# SynthV1.net
KiCad netlist of a schematic drawn in EAGLE
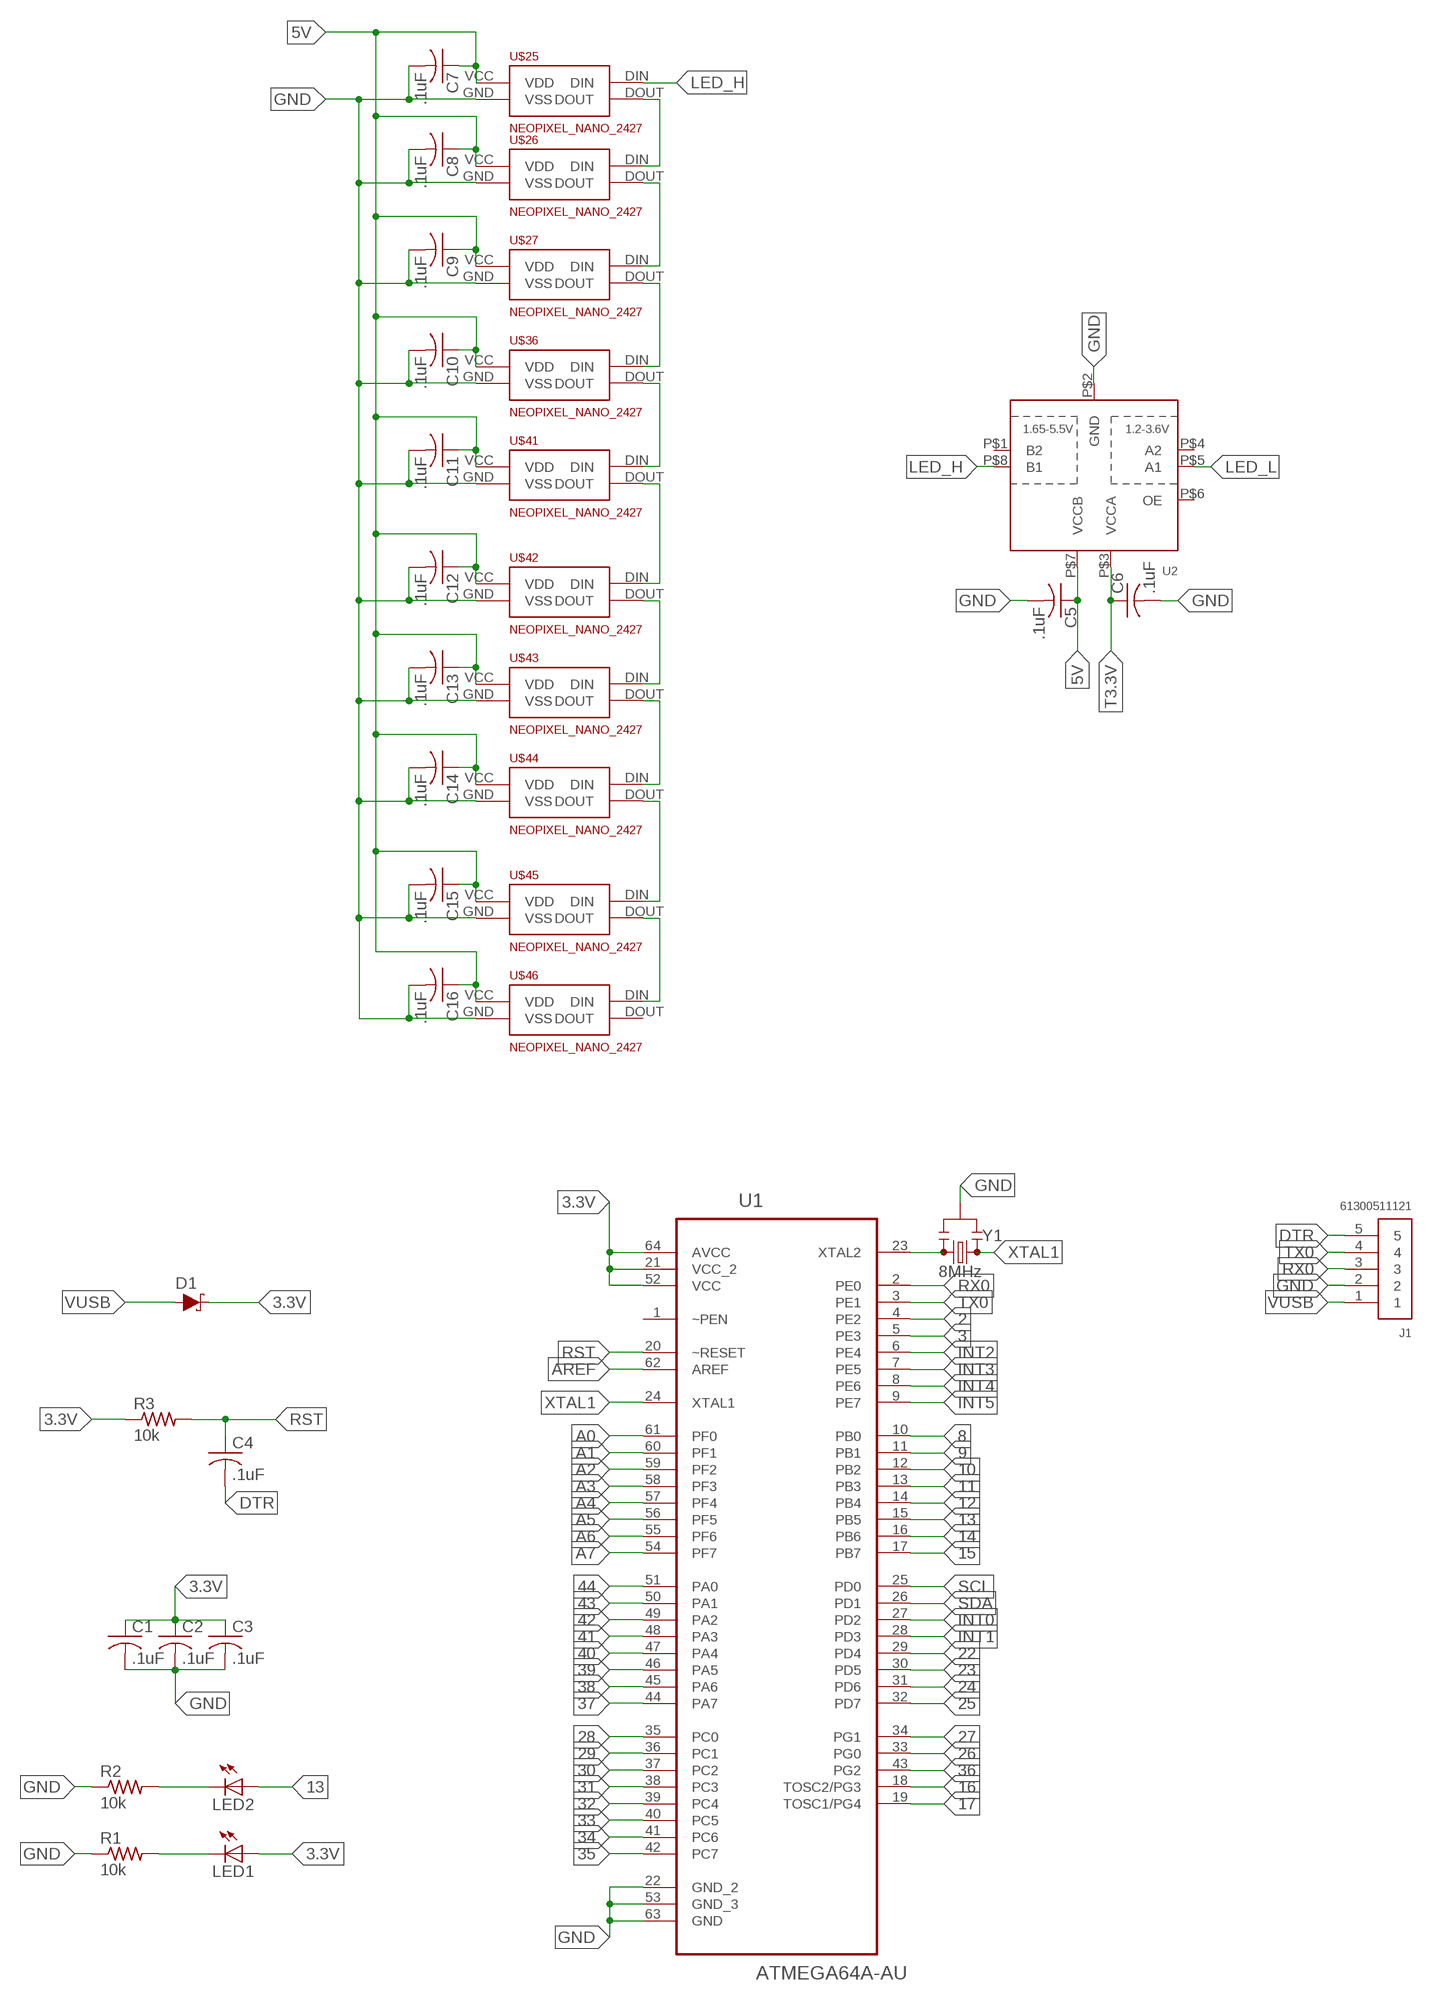
[diagram p0: schematic, sheet 1, part 1 of 2]
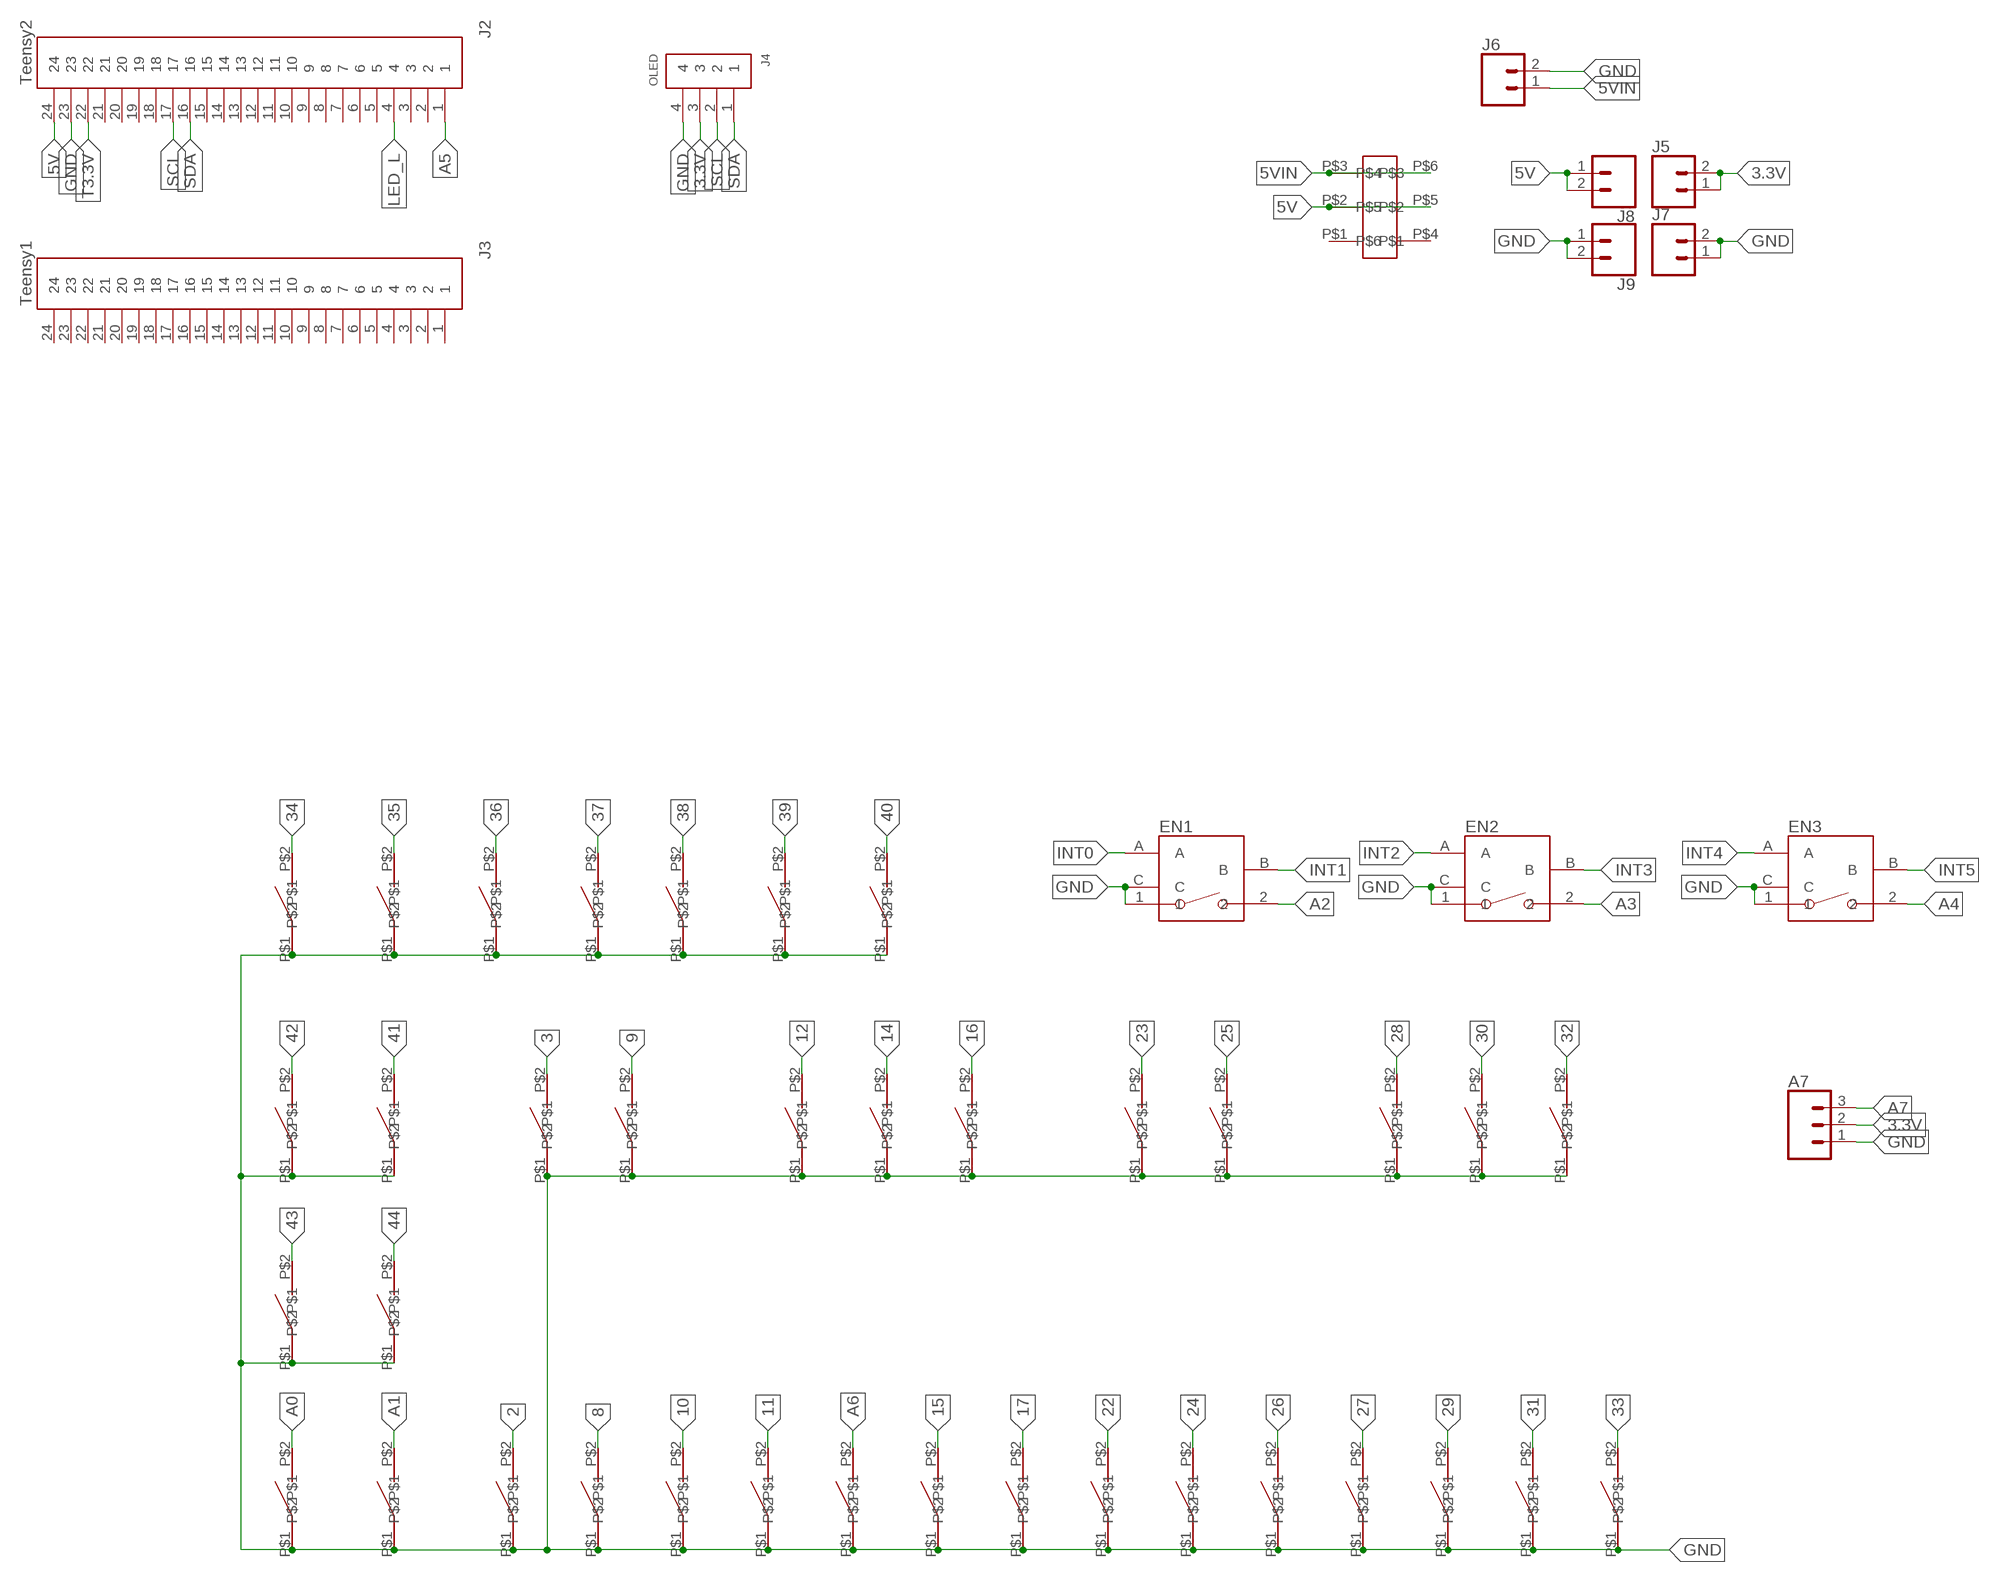
[diagram p1: schematic, sheet 1, part 2 of 2]

(export (version "E")
  (design (tool "Eeschema 10.0.6"))
  (components
    (comp (ref "38")
      (value "BUTTONPAD")
      (footprint "eagle-import:BUTTONPAD")
      (fields (field (name "SPICEPREFIX") "B"))
      (libsource (lib "eagle-import") (part "BUTTONPAD"))
    )
    (comp (ref "A7")
      (value "CONN_03")
      (footprint "eagle-import:1X03")
      (libsource (lib "eagle-import") (part "CONN_03"))
    )
    (comp (ref "C1")
      (value ".1uF")
      (footprint "eagle-import:C0805")
      (libsource (lib "eagle-import") (part "C-USC0805"))
    )
    (comp (ref "C2")
      (value ".1uF")
      (footprint "eagle-import:C0805")
      (libsource (lib "eagle-import") (part "C-USC0805"))
    )
    (comp (ref "C3")
      (value ".1uF")
      (footprint "eagle-import:C0805")
      (libsource (lib "eagle-import") (part "C-USC0805"))
    )
    (comp (ref "C4")
      (value ".1uF")
      (footprint "eagle-import:C0805")
      (libsource (lib "eagle-import") (part "C-USC0805"))
    )
    (comp (ref "C5")
      (value ".1uF")
      (footprint "eagle-import:C0805")
      (libsource (lib "eagle-import") (part "C-USC0805"))
    )
    (comp (ref "C6")
      (value ".1uF")
      (footprint "eagle-import:C0805")
      (libsource (lib "eagle-import") (part "C-USC0805"))
    )
    (comp (ref "C7")
      (value ".1uF")
      (footprint "eagle-import:C0805")
      (libsource (lib "eagle-import") (part "C-USC0805"))
    )
    (comp (ref "C8")
      (value ".1uF")
      (footprint "eagle-import:C0805")
      (libsource (lib "eagle-import") (part "C-USC0805"))
    )
    (comp (ref "C9")
      (value ".1uF")
      (footprint "eagle-import:C0805")
      (libsource (lib "eagle-import") (part "C-USC0805"))
    )
    (comp (ref "C10")
      (value ".1uF")
      (footprint "eagle-import:C0805")
      (libsource (lib "eagle-import") (part "C-USC0805"))
    )
    (comp (ref "C11")
      (value ".1uF")
      (footprint "eagle-import:C0805")
      (libsource (lib "eagle-import") (part "C-USC0805"))
    )
    (comp (ref "C12")
      (value ".1uF")
      (footprint "eagle-import:C0805")
      (libsource (lib "eagle-import") (part "C-USC0805"))
    )
    (comp (ref "C13")
      (value ".1uF")
      (footprint "eagle-import:C0805")
      (libsource (lib "eagle-import") (part "C-USC0805"))
    )
    (comp (ref "C14")
      (value ".1uF")
      (footprint "eagle-import:C0805")
      (libsource (lib "eagle-import") (part "C-USC0805"))
    )
    (comp (ref "C15")
      (value ".1uF")
      (footprint "eagle-import:C0805")
      (libsource (lib "eagle-import") (part "C-USC0805"))
    )
    (comp (ref "C16")
      (value ".1uF")
      (footprint "eagle-import:C0805")
      (libsource (lib "eagle-import") (part "C-USC0805"))
    )
    (comp (ref "D1")
      (value "0.5A/40V/420mV")
      (footprint "eagle-import:SOD-323")
      (libsource (lib "eagle-import") (part "DIODE-SCHOTTKY-PMEG4005EJ"))
    )
    (comp (ref "EN1")
      (value "PEC11R-4215K-S0024")
      (footprint "eagle-import:PEC11R-4215K-S0024")
      (fields
        (field (name "DIGIKEY_PARTNO") "PEC11R-4215K-S0024-ND")
        (field (name "MANUFACTURER") "Bourns Inc.")
        (field (name "SPICEPREFIX") "X")
        (field (name "CREATED_BY") "PCBLayout.com")
      )
      (libsource (lib "eagle-import") (part "PEC11R-4215K-S0024"))
    )
    (comp (ref "EN2")
      (value "PEC11R-4215K-S0024")
      (footprint "eagle-import:PEC11R-4215K-S0024")
      (fields
        (field (name "DIGIKEY_PARTNO") "PEC11R-4215K-S0024-ND")
        (field (name "MANUFACTURER") "Bourns Inc.")
        (field (name "SPICEPREFIX") "X")
        (field (name "CREATED_BY") "PCBLayout.com")
      )
      (libsource (lib "eagle-import") (part "PEC11R-4215K-S0024"))
    )
    (comp (ref "EN3")
      (value "PEC11R-4215K-S0024")
      (footprint "eagle-import:PEC11R-4215K-S0024")
      (fields
        (field (name "DIGIKEY_PARTNO") "PEC11R-4215K-S0024-ND")
        (field (name "MANUFACTURER") "Bourns Inc.")
        (field (name "SPICEPREFIX") "X")
        (field (name "CREATED_BY") "PCBLayout.com")
      )
      (libsource (lib "eagle-import") (part "PEC11R-4215K-S0024"))
    )
    (comp (ref "J1")
      (value "61300511121")
      (footprint "eagle-import:61300511121")
      (fields
        (field (name "DIGI_KEY_PART_NUMBER") "732-5318-ND")
        (field (name "MANUFACTURER") "Wurth Electronics Inc.")
        (field (name "CREATED_BY") "PCBLayout.com")
      )
      (libsource (lib "eagle-import") (part "61300511121"))
    )
    (comp (ref "J2")
      (value "Teensy2")
      (footprint "eagle-import:61302411121")
      (fields
        (field (name "DIGIKEY_PART_NUMBER") "732-5331-ND")
        (field (name "MANUFACTURER") "Wurth Electronics Inc.")
        (field (name "MPN") "61302411121")
        (field (name "CREATED_BY") "PCBLayout.com")
      )
      (libsource (lib "eagle-import") (part "61302411121"))
    )
    (comp (ref "J3")
      (value "Teensy1")
      (footprint "eagle-import:61302411121")
      (fields
        (field (name "DIGIKEY_PART_NUMBER") "732-5331-ND")
        (field (name "MANUFACTURER") "Wurth Electronics Inc.")
        (field (name "MPN") "61302411121")
        (field (name "CREATED_BY") "PCBLayout.com")
      )
      (libsource (lib "eagle-import") (part "61302411121"))
    )
    (comp (ref "J4")
      (value "OLED")
      (footprint "eagle-import:61300411121")
      (fields
        (field (name "DIGI_KEY_PART_NUMBER") "732-5317-ND")
        (field (name "MANUFACTURER") "Wurth Electronics Inc.")
        (field (name "MPN") "61300411121")
        (field (name "CREATED_BY") "PCBLayout.com")
      )
      (libsource (lib "eagle-import") (part "61300411121"))
    )
    (comp (ref "J5")
      (value "CONN_02")
      (footprint "eagle-import:1X02")
      (libsource (lib "eagle-import") (part "CONN_02"))
    )
    (comp (ref "J6")
      (value "CONN_02POLAR")
      (footprint "eagle-import:MOLEX-1X2")
      (libsource (lib "eagle-import") (part "CONN_02POLAR"))
    )
    (comp (ref "J7")
      (value "CONN_02")
      (footprint "eagle-import:1X02")
      (libsource (lib "eagle-import") (part "CONN_02"))
    )
    (comp (ref "J8")
      (value "CONN_02")
      (footprint "eagle-import:1X02")
      (libsource (lib "eagle-import") (part "CONN_02"))
    )
    (comp (ref "J9")
      (value "CONN_02")
      (footprint "eagle-import:1X02")
      (libsource (lib "eagle-import") (part "CONN_02"))
    )
    (comp (ref "LED1")
      (value "LEDCHIPLED_0805")
      (footprint "eagle-import:CHIPLED_0805")
      (libsource (lib "eagle-import") (part "LEDCHIPLED_0805"))
    )
    (comp (ref "LED2")
      (value "LEDCHIPLED_0805")
      (footprint "eagle-import:CHIPLED_0805")
      (libsource (lib "eagle-import") (part "LEDCHIPLED_0805"))
    )
    (comp (ref "R1")
      (value "10k")
      (footprint "eagle-import:R0805")
      (libsource (lib "eagle-import") (part "R-US_R0805"))
    )
    (comp (ref "R2")
      (value "10k")
      (footprint "eagle-import:R0805")
      (libsource (lib "eagle-import") (part "R-US_R0805"))
    )
    (comp (ref "R3")
      (value "10k")
      (footprint "eagle-import:R0805")
      (libsource (lib "eagle-import") (part "R-US_R0805"))
    )
    (comp (ref "U$1")
      (value "BUTTONPAD")
      (footprint "eagle-import:BUTTONPAD")
      (libsource (lib "eagle-import") (part "BUTTONPAD"))
    )
    (comp (ref "U$2")
      (value "BUTTONPAD")
      (footprint "eagle-import:BUTTONPAD")
      (libsource (lib "eagle-import") (part "BUTTONPAD"))
    )
    (comp (ref "U$3")
      (value "BUTTONPAD")
      (footprint "eagle-import:BUTTONPAD")
      (libsource (lib "eagle-import") (part "BUTTONPAD"))
    )
    (comp (ref "U$4")
      (value "BUTTONPAD")
      (footprint "eagle-import:BUTTONPAD")
      (libsource (lib "eagle-import") (part "BUTTONPAD"))
    )
    (comp (ref "U$5")
      (value "BUTTONPAD")
      (footprint "eagle-import:BUTTONPAD")
      (libsource (lib "eagle-import") (part "BUTTONPAD"))
    )
    (comp (ref "U$6")
      (value "BUTTONPAD")
      (footprint "eagle-import:BUTTONPAD")
      (libsource (lib "eagle-import") (part "BUTTONPAD"))
    )
    (comp (ref "U$7")
      (value "BUTTONPAD")
      (footprint "eagle-import:BUTTONPAD")
      (libsource (lib "eagle-import") (part "BUTTONPAD"))
    )
    (comp (ref "U$8")
      (value "BUTTONPAD")
      (footprint "eagle-import:BUTTONPAD")
      (libsource (lib "eagle-import") (part "BUTTONPAD"))
    )
    (comp (ref "U$9")
      (value "BUTTONPAD")
      (footprint "eagle-import:BUTTONPAD")
      (libsource (lib "eagle-import") (part "BUTTONPAD"))
    )
    (comp (ref "U$10")
      (value "BUTTONPAD")
      (footprint "eagle-import:BUTTONPAD")
      (libsource (lib "eagle-import") (part "BUTTONPAD"))
    )
    (comp (ref "U$11")
      (value "BUTTONPAD")
      (footprint "eagle-import:BUTTONPAD")
      (libsource (lib "eagle-import") (part "BUTTONPAD"))
    )
    (comp (ref "U$12")
      (value "BUTTONPAD")
      (footprint "eagle-import:BUTTONPAD")
      (libsource (lib "eagle-import") (part "BUTTONPAD"))
    )
    (comp (ref "U$13")
      (value "BUTTONPAD")
      (footprint "eagle-import:BUTTONPAD")
      (libsource (lib "eagle-import") (part "BUTTONPAD"))
    )
    (comp (ref "U$14")
      (value "BUTTONPAD")
      (footprint "eagle-import:BUTTONPAD")
      (libsource (lib "eagle-import") (part "BUTTONPAD"))
    )
    (comp (ref "U$15")
      (value "BUTTONPAD")
      (footprint "eagle-import:BUTTONPAD")
      (libsource (lib "eagle-import") (part "BUTTONPAD"))
    )
    (comp (ref "U$16")
      (value "BUTTONPAD")
      (footprint "eagle-import:BUTTONPAD")
      (libsource (lib "eagle-import") (part "BUTTONPAD"))
    )
    (comp (ref "U$17")
      (value "BUTTONPAD")
      (footprint "eagle-import:BUTTONPAD")
      (libsource (lib "eagle-import") (part "BUTTONPAD"))
    )
    (comp (ref "U$18")
      (value "BUTTONPAD")
      (footprint "eagle-import:BUTTONPAD")
      (libsource (lib "eagle-import") (part "BUTTONPAD"))
    )
    (comp (ref "U$19")
      (value "BUTTONPAD")
      (footprint "eagle-import:BUTTONPAD")
      (libsource (lib "eagle-import") (part "BUTTONPAD"))
    )
    (comp (ref "U$20")
      (value "BUTTONPAD")
      (footprint "eagle-import:BUTTONPAD")
      (libsource (lib "eagle-import") (part "BUTTONPAD"))
    )
    (comp (ref "U$21")
      (value "BUTTONPAD")
      (footprint "eagle-import:BUTTONPAD")
      (libsource (lib "eagle-import") (part "BUTTONPAD"))
    )
    (comp (ref "U$22")
      (value "BUTTONPAD")
      (footprint "eagle-import:BUTTONPAD")
      (libsource (lib "eagle-import") (part "BUTTONPAD"))
    )
    (comp (ref "U$23")
      (value "BUTTONPAD")
      (footprint "eagle-import:BUTTONPAD")
      (libsource (lib "eagle-import") (part "BUTTONPAD"))
    )
    (comp (ref "U$24")
      (value "BUTTONPAD")
      (footprint "eagle-import:BUTTONPAD")
      (libsource (lib "eagle-import") (part "BUTTONPAD"))
    )
    (comp (ref "U$25")
      (value "NEOPIXEL_NANO_2427")
      (footprint "eagle-import:SK6805-2427")
      (libsource (lib "eagle-import") (part "NEOPIXEL_NANO_2427"))
    )
    (comp (ref "U$26")
      (value "NEOPIXEL_NANO_2427")
      (footprint "eagle-import:SK6805-2427")
      (libsource (lib "eagle-import") (part "NEOPIXEL_NANO_2427"))
    )
    (comp (ref "U$27")
      (value "NEOPIXEL_NANO_2427")
      (footprint "eagle-import:SK6805-2427")
      (libsource (lib "eagle-import") (part "NEOPIXEL_NANO_2427"))
    )
    (comp (ref "U$28")
      (value "BUTTONPAD")
      (footprint "eagle-import:BUTTONPAD")
      (libsource (lib "eagle-import") (part "BUTTONPAD"))
    )
    (comp (ref "U$29")
      (value "BUTTONPAD")
      (footprint "eagle-import:BUTTONPAD")
      (fields (field (name "SPICEPREFIX") "B"))
      (libsource (lib "eagle-import") (part "BUTTONPAD"))
    )
    (comp (ref "U$30")
      (value "BUTTONPAD")
      (footprint "eagle-import:BUTTONPAD")
      (libsource (lib "eagle-import") (part "BUTTONPAD"))
    )
    (comp (ref "U$31")
      (value "BUTTONPAD")
      (footprint "eagle-import:BUTTONPAD")
      (libsource (lib "eagle-import") (part "BUTTONPAD"))
    )
    (comp (ref "U$32")
      (value "BUTTONPAD")
      (footprint "eagle-import:BUTTONPAD")
      (libsource (lib "eagle-import") (part "BUTTONPAD"))
    )
    (comp (ref "U$33")
      (value "BUTTONPAD")
      (footprint "eagle-import:BUTTONPAD")
      (libsource (lib "eagle-import") (part "BUTTONPAD"))
    )
    (comp (ref "U$34")
      (value "BUTTONPAD")
      (footprint "eagle-import:BUTTONPAD")
      (fields (field (name "SPICEPREFIX") "B"))
      (libsource (lib "eagle-import") (part "BUTTONPAD"))
    )
    (comp (ref "U$35")
      (value "BUTTONPAD")
      (footprint "eagle-import:BUTTONPAD")
      (fields (field (name "SPICEPREFIX") "B"))
      (libsource (lib "eagle-import") (part "BUTTONPAD"))
    )
    (comp (ref "U$36")
      (value "NEOPIXEL_NANO_2427")
      (footprint "eagle-import:SK6805-2427")
      (libsource (lib "eagle-import") (part "NEOPIXEL_NANO_2427"))
    )
    (comp (ref "U$37")
      (value "BUTTONPAD")
      (footprint "eagle-import:BUTTONPAD")
      (fields (field (name "SPICEPREFIX") "B"))
      (libsource (lib "eagle-import") (part "BUTTONPAD"))
    )
    (comp (ref "U$38")
      (value "BUTTONPAD")
      (footprint "eagle-import:BUTTONPAD")
      (fields (field (name "SPICEPREFIX") "B"))
      (libsource (lib "eagle-import") (part "BUTTONPAD"))
    )
    (comp (ref "U$39")
      (value "BUTTONPAD")
      (footprint "eagle-import:BUTTONPAD")
      (fields (field (name "SPICEPREFIX") "B"))
      (libsource (lib "eagle-import") (part "BUTTONPAD"))
    )
    (comp (ref "U$40")
      (value "BUTTONPAD")
      (footprint "eagle-import:BUTTONPAD")
      (fields (field (name "SPICEPREFIX") "B"))
      (libsource (lib "eagle-import") (part "BUTTONPAD"))
    )
    (comp (ref "U$41")
      (value "NEOPIXEL_NANO_2427")
      (footprint "eagle-import:SK6805-2427")
      (libsource (lib "eagle-import") (part "NEOPIXEL_NANO_2427"))
    )
    (comp (ref "U$42")
      (value "NEOPIXEL_NANO_2427")
      (footprint "eagle-import:SK6805-2427")
      (libsource (lib "eagle-import") (part "NEOPIXEL_NANO_2427"))
    )
    (comp (ref "U$43")
      (value "NEOPIXEL_NANO_2427")
      (footprint "eagle-import:SK6805-2427")
      (libsource (lib "eagle-import") (part "NEOPIXEL_NANO_2427"))
    )
    (comp (ref "U$44")
      (value "NEOPIXEL_NANO_2427")
      (footprint "eagle-import:SK6805-2427")
      (libsource (lib "eagle-import") (part "NEOPIXEL_NANO_2427"))
    )
    (comp (ref "U$45")
      (value "NEOPIXEL_NANO_2427")
      (footprint "eagle-import:SK6805-2427")
      (libsource (lib "eagle-import") (part "NEOPIXEL_NANO_2427"))
    )
    (comp (ref "U$46")
      (value "NEOPIXEL_NANO_2427")
      (footprint "eagle-import:SK6805-2427")
      (libsource (lib "eagle-import") (part "NEOPIXEL_NANO_2427"))
    )
    (comp (ref "U$47")
      (value "JS202011JAQN")
      (footprint "eagle-import:JS202011JAQN")
      (libsource (lib "eagle-import") (part "JS202011JAQN"))
    )
    (comp (ref "U1")
      (value "ATMEGA64A-AU")
      (footprint "eagle-import:QFP80P1600X1600X120-64N")
      (fields (field (name "DIGI-KEY_PART_NUMBER") "ATMEGA64A-AURTR-ND") (field (name "MF") "Microchip"))
      (libsource (lib "eagle-import") (part "ATMEGA64A-AU"))
    )
    (comp (ref "U2")
      (value "TXS0102")
      (footprint "eagle-import:VFSOP-8")
      (libsource (lib "eagle-import") (part "TXS0102"))
    )
    (comp (ref "Y1")
      (value "8MHz")
      (footprint "eagle-import:RESONATOR-SMD-3.2X1.3")
      (libsource (lib "eagle-import") (part "RESONATOR-8MHZSMD_3.2X1.3"))
    )
  )
  (nets
    (net (code "1") (name "2") (class "Default")
      (node (ref "U$1") (pin "P$2") (pinfunction "P$2_P$2") (pintype "bidirectional"))
      (node (ref "U1") (pin "4") (pinfunction "PE2_4") (pintype "bidirectional"))
    )
    (net (code "2") (name "3") (class "Default")
      (node (ref "U$15") (pin "P$2") (pinfunction "P$2_P$2") (pintype "bidirectional"))
      (node (ref "U1") (pin "5") (pinfunction "PE3_5") (pintype "bidirectional"))
    )
    (net (code "3") (name "3.3V") (class "Default")
      (node (ref "A7") (pin "2") (pinfunction "2_2") (pintype "passive"))
      (node (ref "C1") (pin "1") (pinfunction "1_1") (pintype "passive"))
      (node (ref "C2") (pin "1") (pinfunction "1_1") (pintype "passive"))
      (node (ref "C3") (pin "1") (pinfunction "1_1") (pintype "passive"))
      (node (ref "D1") (pin "C") (pinfunction "C_C") (pintype "passive"))
      (node (ref "J4") (pin "3") (pinfunction "3_3") (pintype "passive"))
      (node (ref "J5") (pin "1") (pinfunction "1_1") (pintype "passive"))
      (node (ref "J5") (pin "2") (pinfunction "2_2") (pintype "passive"))
      (node (ref "LED1") (pin "A") (pinfunction "A_A") (pintype "passive"))
      (node (ref "R3") (pin "1") (pinfunction "1_1") (pintype "passive"))
      (node (ref "U1") (pin "21") (pinfunction "VCC_2_21") (pintype "power_in"))
      (node (ref "U1") (pin "52") (pinfunction "VCC_52") (pintype "power_in"))
      (node (ref "U1") (pin "64") (pinfunction "AVCC_64") (pintype "power_in"))
    )
    (net (code "4") (name "5V") (class "Default")
      (node (ref "C10") (pin "1") (pinfunction "1_1") (pintype "passive"))
      (node (ref "C11") (pin "1") (pinfunction "1_1") (pintype "passive"))
      (node (ref "C12") (pin "1") (pinfunction "1_1") (pintype "passive"))
      (node (ref "C13") (pin "1") (pinfunction "1_1") (pintype "passive"))
      (node (ref "C14") (pin "1") (pinfunction "1_1") (pintype "passive"))
      (node (ref "C15") (pin "1") (pinfunction "1_1") (pintype "passive"))
      (node (ref "C16") (pin "1") (pinfunction "1_1") (pintype "passive"))
      (node (ref "C5") (pin "1") (pinfunction "1_1") (pintype "passive"))
      (node (ref "C7") (pin "1") (pinfunction "1_1") (pintype "passive"))
      (node (ref "C8") (pin "1") (pinfunction "1_1") (pintype "passive"))
      (node (ref "C9") (pin "1") (pinfunction "1_1") (pintype "passive"))
      (node (ref "J2") (pin "24") (pinfunction "24_24") (pintype "passive"))
      (node (ref "J8") (pin "1") (pinfunction "1_1") (pintype "passive"))
      (node (ref "J8") (pin "2") (pinfunction "2_2") (pintype "passive"))
      (node (ref "U$25") (pin "VCC") (pinfunction "VDD_VCC") (pintype "bidirectional"))
      (node (ref "U$26") (pin "VCC") (pinfunction "VDD_VCC") (pintype "bidirectional"))
      (node (ref "U$27") (pin "VCC") (pinfunction "VDD_VCC") (pintype "bidirectional"))
      (node (ref "U$36") (pin "VCC") (pinfunction "VDD_VCC") (pintype "bidirectional"))
      (node (ref "U$41") (pin "VCC") (pinfunction "VDD_VCC") (pintype "bidirectional"))
      (node (ref "U$42") (pin "VCC") (pinfunction "VDD_VCC") (pintype "bidirectional"))
      (node (ref "U$43") (pin "VCC") (pinfunction "VDD_VCC") (pintype "bidirectional"))
      (node (ref "U$44") (pin "VCC") (pinfunction "VDD_VCC") (pintype "bidirectional"))
      (node (ref "U$45") (pin "VCC") (pinfunction "VDD_VCC") (pintype "bidirectional"))
      (node (ref "U$46") (pin "VCC") (pinfunction "VDD_VCC") (pintype "bidirectional"))
      (node (ref "U$47") (pin "P$2") (pinfunction "P$2_P$2") (pintype "bidirectional"))
      (node (ref "U$47") (pin "P$5") (pinfunction "P$5_P$5") (pintype "bidirectional"))
      (node (ref "U2") (pin "P$7") (pinfunction "VCCB_P$7") (pintype "bidirectional"))
    )
    (net (code "5") (name "5VIN") (class "Default")
      (node (ref "J6") (pin "1") (pinfunction "1_1") (pintype "passive"))
      (node (ref "U$47") (pin "P$3") (pinfunction "P$3_P$3") (pintype "bidirectional"))
      (node (ref "U$47") (pin "P$6") (pinfunction "P$4_P$6") (pintype "bidirectional"))
    )
    (net (code "6") (name "8") (class "Default")
      (node (ref "U$2") (pin "P$2") (pinfunction "P$2_P$2") (pintype "bidirectional"))
      (node (ref "U1") (pin "10") (pinfunction "PB0_10") (pintype "bidirectional"))
    )
    (net (code "7") (name "9") (class "Default")
      (node (ref "U$16") (pin "P$2") (pinfunction "P$2_P$2") (pintype "bidirectional"))
      (node (ref "U1") (pin "11") (pinfunction "PB1_11") (pintype "bidirectional"))
    )
    (net (code "8") (name "10") (class "Default")
      (node (ref "U$3") (pin "P$2") (pinfunction "P$2_P$2") (pintype "bidirectional"))
      (node (ref "U1") (pin "12") (pinfunction "PB2_12") (pintype "bidirectional"))
    )
    (net (code "9") (name "11") (class "Default")
      (node (ref "U$4") (pin "P$2") (pinfunction "P$2_P$2") (pintype "bidirectional"))
      (node (ref "U1") (pin "13") (pinfunction "PB3_13") (pintype "bidirectional"))
    )
    (net (code "10") (name "12") (class "Default")
      (node (ref "U$17") (pin "P$2") (pinfunction "P$2_P$2") (pintype "bidirectional"))
      (node (ref "U1") (pin "14") (pinfunction "PB4_14") (pintype "bidirectional"))
    )
    (net (code "11") (name "13") (class "Default")
      (node (ref "LED2") (pin "A") (pinfunction "A_A") (pintype "passive"))
      (node (ref "U1") (pin "15") (pinfunction "PB5_15") (pintype "bidirectional"))
    )
    (net (code "12") (name "14") (class "Default")
      (node (ref "U$18") (pin "P$2") (pinfunction "P$2_P$2") (pintype "bidirectional"))
      (node (ref "U1") (pin "16") (pinfunction "PB6_16") (pintype "bidirectional"))
    )
    (net (code "13") (name "15") (class "Default")
      (node (ref "U$6") (pin "P$2") (pinfunction "P$2_P$2") (pintype "bidirectional"))
      (node (ref "U1") (pin "17") (pinfunction "PB7_17") (pintype "bidirectional"))
    )
    (net (code "14") (name "16") (class "Default")
      (node (ref "U$19") (pin "P$2") (pinfunction "P$2_P$2") (pintype "bidirectional"))
      (node (ref "U1") (pin "18") (pinfunction "TOSC2/PG3_18") (pintype "bidirectional"))
    )
    (net (code "15") (name "17") (class "Default")
      (node (ref "U$7") (pin "P$2") (pinfunction "P$2_P$2") (pintype "bidirectional"))
      (node (ref "U1") (pin "19") (pinfunction "TOSC1/PG4_19") (pintype "bidirectional"))
    )
    (net (code "16") (name "22") (class "Default")
      (node (ref "U$8") (pin "P$2") (pinfunction "P$2_P$2") (pintype "bidirectional"))
      (node (ref "U1") (pin "29") (pinfunction "PD4_29") (pintype "bidirectional"))
    )
    (net (code "17") (name "23") (class "Default")
      (node (ref "U$20") (pin "P$2") (pinfunction "P$2_P$2") (pintype "bidirectional"))
      (node (ref "U1") (pin "30") (pinfunction "PD5_30") (pintype "bidirectional"))
    )
    (net (code "18") (name "24") (class "Default")
      (node (ref "U$9") (pin "P$2") (pinfunction "P$2_P$2") (pintype "bidirectional"))
      (node (ref "U1") (pin "31") (pinfunction "PD6_31") (pintype "bidirectional"))
    )
    (net (code "19") (name "25") (class "Default")
      (node (ref "U$21") (pin "P$2") (pinfunction "P$2_P$2") (pintype "bidirectional"))
      (node (ref "U1") (pin "32") (pinfunction "PD7_32") (pintype "bidirectional"))
    )
    (net (code "20") (name "26") (class "Default")
      (node (ref "U$10") (pin "P$2") (pinfunction "P$2_P$2") (pintype "bidirectional"))
      (node (ref "U1") (pin "33") (pinfunction "PG0_33") (pintype "bidirectional"))
    )
    (net (code "21") (name "27") (class "Default")
      (node (ref "U$11") (pin "P$2") (pinfunction "P$2_P$2") (pintype "bidirectional"))
      (node (ref "U1") (pin "34") (pinfunction "PG1_34") (pintype "bidirectional"))
    )
    (net (code "22") (name "28") (class "Default")
      (node (ref "U$22") (pin "P$2") (pinfunction "P$2_P$2") (pintype "bidirectional"))
      (node (ref "U1") (pin "35") (pinfunction "PC0_35") (pintype "bidirectional"))
    )
    (net (code "23") (name "29") (class "Default")
      (node (ref "U$12") (pin "P$2") (pinfunction "P$2_P$2") (pintype "bidirectional"))
      (node (ref "U1") (pin "36") (pinfunction "PC1_36") (pintype "bidirectional"))
    )
    (net (code "24") (name "30") (class "Default")
      (node (ref "U$23") (pin "P$2") (pinfunction "P$2_P$2") (pintype "bidirectional"))
      (node (ref "U1") (pin "37") (pinfunction "PC2_37") (pintype "bidirectional"))
    )
    (net (code "25") (name "31") (class "Default")
      (node (ref "U$13") (pin "P$2") (pinfunction "P$2_P$2") (pintype "bidirectional"))
      (node (ref "U1") (pin "38") (pinfunction "PC3_38") (pintype "bidirectional"))
    )
    (net (code "26") (name "32") (class "Default")
      (node (ref "U$24") (pin "P$2") (pinfunction "P$2_P$2") (pintype "bidirectional"))
      (node (ref "U1") (pin "39") (pinfunction "PC4_39") (pintype "bidirectional"))
    )
    (net (code "27") (name "33") (class "Default")
      (node (ref "U$14") (pin "P$2") (pinfunction "P$2_P$2") (pintype "bidirectional"))
      (node (ref "U1") (pin "40") (pinfunction "PC5_40") (pintype "bidirectional"))
    )
    (net (code "28") (name "34") (class "Default")
      (node (ref "U$37") (pin "P$2") (pinfunction "P$2_P$2") (pintype "bidirectional"))
      (node (ref "U1") (pin "41") (pinfunction "PC6_41") (pintype "bidirectional"))
    )
    (net (code "29") (name "35") (class "Default")
      (node (ref "U$38") (pin "P$2") (pinfunction "P$2_P$2") (pintype "bidirectional"))
      (node (ref "U1") (pin "42") (pinfunction "PC7_42") (pintype "bidirectional"))
    )
    (net (code "30") (name "36") (class "Default")
      (node (ref "U$39") (pin "P$2") (pinfunction "P$2_P$2") (pintype "bidirectional"))
      (node (ref "U1") (pin "43") (pinfunction "PG2_43") (pintype "bidirectional"))
    )
    (net (code "31") (name "37") (class "Default")
      (node (ref "U$40") (pin "P$2") (pinfunction "P$2_P$2") (pintype "bidirectional"))
      (node (ref "U1") (pin "44") (pinfunction "PA7_44") (pintype "bidirectional"))
    )
    (net (code "32") (name "38") (class "Default")
      (node (ref "38") (pin "P$2") (pinfunction "P$2_P$2") (pintype "bidirectional"))
      (node (ref "U1") (pin "45") (pinfunction "PA6_45") (pintype "bidirectional"))
    )
    (net (code "33") (name "39") (class "Default")
      (node (ref "U$35") (pin "P$2") (pinfunction "P$2_P$2") (pintype "bidirectional"))
      (node (ref "U1") (pin "46") (pinfunction "PA5_46") (pintype "bidirectional"))
    )
    (net (code "34") (name "40") (class "Default")
      (node (ref "U$34") (pin "P$2") (pinfunction "P$2_P$2") (pintype "bidirectional"))
      (node (ref "U1") (pin "47") (pinfunction "PA4_47") (pintype "bidirectional"))
    )
    (net (code "35") (name "41") (class "Default")
      (node (ref "U$33") (pin "P$2") (pinfunction "P$2_P$2") (pintype "bidirectional"))
      (node (ref "U1") (pin "48") (pinfunction "PA3_48") (pintype "bidirectional"))
    )
    (net (code "36") (name "42") (class "Default")
      (node (ref "U$29") (pin "P$2") (pinfunction "P$2_P$2") (pintype "bidirectional"))
      (node (ref "U1") (pin "49") (pinfunction "PA2_49") (pintype "bidirectional"))
    )
    (net (code "37") (name "43") (class "Default")
      (node (ref "U$30") (pin "P$2") (pinfunction "P$2_P$2") (pintype "bidirectional"))
      (node (ref "U1") (pin "50") (pinfunction "PA1_50") (pintype "bidirectional"))
    )
    (net (code "38") (name "44") (class "Default")
      (node (ref "U$31") (pin "P$2") (pinfunction "P$2_P$2") (pintype "bidirectional"))
      (node (ref "U1") (pin "51") (pinfunction "PA0_51") (pintype "bidirectional"))
    )
    (net (code "39") (name "A0") (class "Default")
      (node (ref "U$32") (pin "P$2") (pinfunction "P$2_P$2") (pintype "bidirectional"))
      (node (ref "U1") (pin "61") (pinfunction "PF0_61") (pintype "bidirectional"))
    )
    (net (code "40") (name "A1") (class "Default")
      (node (ref "U$28") (pin "P$2") (pinfunction "P$2_P$2") (pintype "bidirectional"))
      (node (ref "U1") (pin "60") (pinfunction "PF1_60") (pintype "bidirectional"))
    )
    (net (code "41") (name "A2") (class "Default")
      (node (ref "EN1") (pin "2") (pinfunction "2_2") (pintype "passive"))
      (node (ref "U1") (pin "59") (pinfunction "PF2_59") (pintype "bidirectional"))
    )
    (net (code "42") (name "A3") (class "Default")
      (node (ref "EN2") (pin "2") (pinfunction "2_2") (pintype "passive"))
      (node (ref "U1") (pin "58") (pinfunction "PF3_58") (pintype "bidirectional"))
    )
    (net (code "43") (name "A4") (class "Default")
      (node (ref "EN3") (pin "2") (pinfunction "2_2") (pintype "passive"))
      (node (ref "U1") (pin "57") (pinfunction "PF4_57") (pintype "bidirectional"))
    )
    (net (code "44") (name "A5") (class "Default")
      (node (ref "J2") (pin "1") (pinfunction "1_1") (pintype "passive"))
      (node (ref "U1") (pin "56") (pinfunction "PF5_56") (pintype "bidirectional"))
    )
    (net (code "45") (name "A6") (class "Default")
      (node (ref "U$5") (pin "P$2") (pinfunction "P$2_P$2") (pintype "bidirectional"))
      (node (ref "U1") (pin "55") (pinfunction "PF6_55") (pintype "bidirectional"))
    )
    (net (code "46") (name "A7") (class "Default")
      (node (ref "A7") (pin "3") (pinfunction "3_3") (pintype "passive"))
      (node (ref "U1") (pin "54") (pinfunction "PF7_54") (pintype "bidirectional"))
    )
    (net (code "47") (name "AREF") (class "Default")
      (node (ref "U1") (pin "62") (pinfunction "AREF_62") (pintype "input"))
    )
    (net (code "48") (name "DTR") (class "Default")
      (node (ref "C4") (pin "2") (pinfunction "2_2") (pintype "passive"))
      (node (ref "J1") (pin "5") (pinfunction "5_5") (pintype "passive"))
    )
    (net (code "49") (name "GND") (class "Default")
      (node (ref "38") (pin "P$1") (pinfunction "P$1_P$1") (pintype "bidirectional"))
      (node (ref "A7") (pin "1") (pinfunction "1_1") (pintype "passive"))
      (node (ref "C1") (pin "2") (pinfunction "2_2") (pintype "passive"))
      (node (ref "C10") (pin "2") (pinfunction "2_2") (pintype "passive"))
      (node (ref "C11") (pin "2") (pinfunction "2_2") (pintype "passive"))
      (node (ref "C12") (pin "2") (pinfunction "2_2") (pintype "passive"))
      (node (ref "C13") (pin "2") (pinfunction "2_2") (pintype "passive"))
      (node (ref "C14") (pin "2") (pinfunction "2_2") (pintype "passive"))
      (node (ref "C15") (pin "2") (pinfunction "2_2") (pintype "passive"))
      (node (ref "C16") (pin "2") (pinfunction "2_2") (pintype "passive"))
      (node (ref "C2") (pin "2") (pinfunction "2_2") (pintype "passive"))
      (node (ref "C3") (pin "2") (pinfunction "2_2") (pintype "passive"))
      (node (ref "C5") (pin "2") (pinfunction "2_2") (pintype "passive"))
      (node (ref "C6") (pin "2") (pinfunction "2_2") (pintype "passive"))
      (node (ref "C7") (pin "2") (pinfunction "2_2") (pintype "passive"))
      (node (ref "C8") (pin "2") (pinfunction "2_2") (pintype "passive"))
      (node (ref "C9") (pin "2") (pinfunction "2_2") (pintype "passive"))
      (node (ref "EN1") (pin "1") (pinfunction "1_1") (pintype "passive"))
      (node (ref "EN1") (pin "C") (pinfunction "C_C") (pintype "passive"))
      (node (ref "EN2") (pin "1") (pinfunction "1_1") (pintype "passive"))
      (node (ref "EN2") (pin "C") (pinfunction "C_C") (pintype "passive"))
      (node (ref "EN3") (pin "1") (pinfunction "1_1") (pintype "passive"))
      (node (ref "EN3") (pin "C") (pinfunction "C_C") (pintype "passive"))
      (node (ref "J1") (pin "2") (pinfunction "2_2") (pintype "passive"))
      (node (ref "J2") (pin "23") (pinfunction "23_23") (pintype "passive"))
      (node (ref "J4") (pin "4") (pinfunction "4_4") (pintype "passive"))
      (node (ref "J6") (pin "2") (pinfunction "2_2") (pintype "passive"))
      (node (ref "J7") (pin "1") (pinfunction "1_1") (pintype "passive"))
      (node (ref "J7") (pin "2") (pinfunction "2_2") (pintype "passive"))
      (node (ref "J9") (pin "1") (pinfunction "1_1") (pintype "passive"))
      (node (ref "J9") (pin "2") (pinfunction "2_2") (pintype "passive"))
      (node (ref "R1") (pin "1") (pinfunction "1_1") (pintype "passive"))
      (node (ref "R2") (pin "1") (pinfunction "1_1") (pintype "passive"))
      (node (ref "U$1") (pin "P$1") (pinfunction "P$1_P$1") (pintype "bidirectional"))
      (node (ref "U$10") (pin "P$1") (pinfunction "P$1_P$1") (pintype "bidirectional"))
      (node (ref "U$11") (pin "P$1") (pinfunction "P$1_P$1") (pintype "bidirectional"))
      (node (ref "U$12") (pin "P$1") (pinfunction "P$1_P$1") (pintype "bidirectional"))
      (node (ref "U$13") (pin "P$1") (pinfunction "P$1_P$1") (pintype "bidirectional"))
      (node (ref "U$14") (pin "P$1") (pinfunction "P$1_P$1") (pintype "bidirectional"))
      (node (ref "U$15") (pin "P$1") (pinfunction "P$1_P$1") (pintype "bidirectional"))
      (node (ref "U$16") (pin "P$1") (pinfunction "P$1_P$1") (pintype "bidirectional"))
      (node (ref "U$17") (pin "P$1") (pinfunction "P$1_P$1") (pintype "bidirectional"))
      (node (ref "U$18") (pin "P$1") (pinfunction "P$1_P$1") (pintype "bidirectional"))
      (node (ref "U$19") (pin "P$1") (pinfunction "P$1_P$1") (pintype "bidirectional"))
      (node (ref "U$2") (pin "P$1") (pinfunction "P$1_P$1") (pintype "bidirectional"))
      (node (ref "U$20") (pin "P$1") (pinfunction "P$1_P$1") (pintype "bidirectional"))
      (node (ref "U$21") (pin "P$1") (pinfunction "P$1_P$1") (pintype "bidirectional"))
      (node (ref "U$22") (pin "P$1") (pinfunction "P$1_P$1") (pintype "bidirectional"))
      (node (ref "U$23") (pin "P$1") (pinfunction "P$1_P$1") (pintype "bidirectional"))
      (node (ref "U$24") (pin "P$1") (pinfunction "P$1_P$1") (pintype "bidirectional"))
      (node (ref "U$25") (pin "GND") (pinfunction "VSS_GND") (pintype "bidirectional"))
      (node (ref "U$26") (pin "GND") (pinfunction "VSS_GND") (pintype "bidirectional"))
      (node (ref "U$27") (pin "GND") (pinfunction "VSS_GND") (pintype "bidirectional"))
      (node (ref "U$28") (pin "P$1") (pinfunction "P$1_P$1") (pintype "bidirectional"))
      (node (ref "U$29") (pin "P$1") (pinfunction "P$1_P$1") (pintype "bidirectional"))
      (node (ref "U$3") (pin "P$1") (pinfunction "P$1_P$1") (pintype "bidirectional"))
      (node (ref "U$30") (pin "P$1") (pinfunction "P$1_P$1") (pintype "bidirectional"))
      (node (ref "U$31") (pin "P$1") (pinfunction "P$1_P$1") (pintype "bidirectional"))
      (node (ref "U$32") (pin "P$1") (pinfunction "P$1_P$1") (pintype "bidirectional"))
      (node (ref "U$33") (pin "P$1") (pinfunction "P$1_P$1") (pintype "bidirectional"))
      (node (ref "U$34") (pin "P$1") (pinfunction "P$1_P$1") (pintype "bidirectional"))
      (node (ref "U$35") (pin "P$1") (pinfunction "P$1_P$1") (pintype "bidirectional"))
      (node (ref "U$36") (pin "GND") (pinfunction "VSS_GND") (pintype "bidirectional"))
      (node (ref "U$37") (pin "P$1") (pinfunction "P$1_P$1") (pintype "bidirectional"))
      (node (ref "U$38") (pin "P$1") (pinfunction "P$1_P$1") (pintype "bidirectional"))
      (node (ref "U$39") (pin "P$1") (pinfunction "P$1_P$1") (pintype "bidirectional"))
      (node (ref "U$4") (pin "P$1") (pinfunction "P$1_P$1") (pintype "bidirectional"))
      (node (ref "U$40") (pin "P$1") (pinfunction "P$1_P$1") (pintype "bidirectional"))
      (node (ref "U$41") (pin "GND") (pinfunction "VSS_GND") (pintype "bidirectional"))
      (node (ref "U$42") (pin "GND") (pinfunction "VSS_GND") (pintype "bidirectional"))
      (node (ref "U$43") (pin "GND") (pinfunction "VSS_GND") (pintype "bidirectional"))
      (node (ref "U$44") (pin "GND") (pinfunction "VSS_GND") (pintype "bidirectional"))
      (node (ref "U$45") (pin "GND") (pinfunction "VSS_GND") (pintype "bidirectional"))
      (node (ref "U$46") (pin "GND") (pinfunction "VSS_GND") (pintype "bidirectional"))
      (node (ref "U$5") (pin "P$1") (pinfunction "P$1_P$1") (pintype "bidirectional"))
      (node (ref "U$6") (pin "P$1") (pinfunction "P$1_P$1") (pintype "bidirectional"))
      (node (ref "U$7") (pin "P$1") (pinfunction "P$1_P$1") (pintype "bidirectional"))
      (node (ref "U$8") (pin "P$1") (pinfunction "P$1_P$1") (pintype "bidirectional"))
      (node (ref "U$9") (pin "P$1") (pinfunction "P$1_P$1") (pintype "bidirectional"))
      (node (ref "U1") (pin "22") (pinfunction "GND_2_22") (pintype "passive"))
      (node (ref "U1") (pin "53") (pinfunction "GND_3_53") (pintype "passive"))
      (node (ref "U1") (pin "63") (pinfunction "GND_63") (pintype "passive"))
      (node (ref "U2") (pin "P$2") (pinfunction "GND_P$2") (pintype "bidirectional"))
      (node (ref "Y1") (pin "2") (pinfunction "2_2") (pintype "passive"))
    )
    (net (code "50") (name "INT0") (class "Default")
      (node (ref "EN1") (pin "A") (pinfunction "A_A") (pintype "passive"))
      (node (ref "U1") (pin "27") (pinfunction "PD2_27") (pintype "bidirectional"))
    )
    (net (code "51") (name "INT1") (class "Default")
      (node (ref "EN1") (pin "B") (pinfunction "B_B") (pintype "passive"))
      (node (ref "U1") (pin "28") (pinfunction "PD3_28") (pintype "bidirectional"))
    )
    (net (code "52") (name "INT2") (class "Default")
      (node (ref "EN2") (pin "A") (pinfunction "A_A") (pintype "passive"))
      (node (ref "U1") (pin "6") (pinfunction "PE4_6") (pintype "bidirectional"))
    )
    (net (code "53") (name "INT3") (class "Default")
      (node (ref "EN2") (pin "B") (pinfunction "B_B") (pintype "passive"))
      (node (ref "U1") (pin "7") (pinfunction "PE5_7") (pintype "bidirectional"))
    )
    (net (code "54") (name "INT4") (class "Default")
      (node (ref "EN3") (pin "A") (pinfunction "A_A") (pintype "passive"))
      (node (ref "U1") (pin "8") (pinfunction "PE6_8") (pintype "bidirectional"))
    )
    (net (code "55") (name "INT5") (class "Default")
      (node (ref "EN3") (pin "B") (pinfunction "B_B") (pintype "passive"))
      (node (ref "U1") (pin "9") (pinfunction "PE7_9") (pintype "bidirectional"))
    )
    (net (code "56") (name "LED_H") (class "Default")
      (node (ref "U$25") (pin "DIN") (pinfunction "DIN_DIN") (pintype "bidirectional"))
      (node (ref "U2") (pin "P$8") (pinfunction "B1_P$8") (pintype "bidirectional"))
    )
    (net (code "57") (name "LED_L") (class "Default")
      (node (ref "J2") (pin "4") (pinfunction "4_4") (pintype "passive"))
      (node (ref "U2") (pin "P$5") (pinfunction "A1_P$5") (pintype "bidirectional"))
    )
    (net (code "58") (name "Net-(LED1-PadC)") (class "Default")
      (node (ref "LED1") (pin "C") (pinfunction "C_C") (pintype "passive"))
      (node (ref "R1") (pin "2") (pinfunction "2_2") (pintype "passive"))
    )
    (net (code "59") (name "Net-(LED2-PadC)") (class "Default")
      (node (ref "LED2") (pin "C") (pinfunction "C_C") (pintype "passive"))
      (node (ref "R2") (pin "2") (pinfunction "2_2") (pintype "passive"))
    )
    (net (code "60") (name "Net-(U$25-PadDOUT)") (class "Default")
      (node (ref "U$25") (pin "DOUT") (pinfunction "DOUT_DOUT") (pintype "bidirectional"))
      (node (ref "U$26") (pin "DIN") (pinfunction "DIN_DIN") (pintype "bidirectional"))
    )
    (net (code "61") (name "Net-(U$26-PadDOUT)") (class "Default")
      (node (ref "U$26") (pin "DOUT") (pinfunction "DOUT_DOUT") (pintype "bidirectional"))
      (node (ref "U$27") (pin "DIN") (pinfunction "DIN_DIN") (pintype "bidirectional"))
    )
    (net (code "62") (name "Net-(U$27-PadDOUT)") (class "Default")
      (node (ref "U$27") (pin "DOUT") (pinfunction "DOUT_DOUT") (pintype "bidirectional"))
      (node (ref "U$36") (pin "DIN") (pinfunction "DIN_DIN") (pintype "bidirectional"))
    )
    (net (code "63") (name "Net-(U$36-PadDOUT)") (class "Default")
      (node (ref "U$36") (pin "DOUT") (pinfunction "DOUT_DOUT") (pintype "bidirectional"))
      (node (ref "U$41") (pin "DIN") (pinfunction "DIN_DIN") (pintype "bidirectional"))
    )
    (net (code "64") (name "Net-(U$41-PadDOUT)") (class "Default")
      (node (ref "U$41") (pin "DOUT") (pinfunction "DOUT_DOUT") (pintype "bidirectional"))
      (node (ref "U$42") (pin "DIN") (pinfunction "DIN_DIN") (pintype "bidirectional"))
    )
    (net (code "65") (name "Net-(U$42-PadDOUT)") (class "Default")
      (node (ref "U$42") (pin "DOUT") (pinfunction "DOUT_DOUT") (pintype "bidirectional"))
      (node (ref "U$43") (pin "DIN") (pinfunction "DIN_DIN") (pintype "bidirectional"))
    )
    (net (code "66") (name "Net-(U$43-PadDOUT)") (class "Default")
      (node (ref "U$43") (pin "DOUT") (pinfunction "DOUT_DOUT") (pintype "bidirectional"))
      (node (ref "U$44") (pin "DIN") (pinfunction "DIN_DIN") (pintype "bidirectional"))
    )
    (net (code "67") (name "Net-(U$44-PadDOUT)") (class "Default")
      (node (ref "U$44") (pin "DOUT") (pinfunction "DOUT_DOUT") (pintype "bidirectional"))
      (node (ref "U$45") (pin "DIN") (pinfunction "DIN_DIN") (pintype "bidirectional"))
    )
    (net (code "68") (name "Net-(U$45-PadDOUT)") (class "Default")
      (node (ref "U$45") (pin "DOUT") (pinfunction "DOUT_DOUT") (pintype "bidirectional"))
      (node (ref "U$46") (pin "DIN") (pinfunction "DIN_DIN") (pintype "bidirectional"))
    )
    (net (code "69") (name "Net-(U1-XTAL2)") (class "Default")
      (node (ref "U1") (pin "23") (pinfunction "XTAL2_23") (pintype "output"))
      (node (ref "Y1") (pin "3") (pinfunction "3_3") (pintype "passive"))
    )
    (net (code "70") (name "RST") (class "Default")
      (node (ref "C4") (pin "1") (pinfunction "1_1") (pintype "passive"))
      (node (ref "R3") (pin "2") (pinfunction "2_2") (pintype "passive"))
      (node (ref "U1") (pin "20") (pinfunction "~{RESET}_20") (pintype "input"))
    )
    (net (code "71") (name "RX0") (class "Default")
      (node (ref "J1") (pin "3") (pinfunction "3_3") (pintype "passive"))
      (node (ref "U1") (pin "2") (pinfunction "PE0_2") (pintype "bidirectional"))
    )
    (net (code "72") (name "SCL") (class "Default")
      (node (ref "J2") (pin "17") (pinfunction "17_17") (pintype "passive"))
      (node (ref "J4") (pin "2") (pinfunction "2_2") (pintype "passive"))
      (node (ref "U1") (pin "25") (pinfunction "PD0_25") (pintype "bidirectional"))
    )
    (net (code "73") (name "SDA") (class "Default")
      (node (ref "J2") (pin "16") (pinfunction "16_16") (pintype "passive"))
      (node (ref "J4") (pin "1") (pinfunction "1_1") (pintype "passive"))
      (node (ref "U1") (pin "26") (pinfunction "PD1_26") (pintype "bidirectional"))
    )
    (net (code "74") (name "T3.3V") (class "Default")
      (node (ref "C6") (pin "1") (pinfunction "1_1") (pintype "passive"))
      (node (ref "J2") (pin "22") (pinfunction "22_22") (pintype "passive"))
      (node (ref "U2") (pin "P$3") (pinfunction "VCCA_P$3") (pintype "bidirectional"))
    )
    (net (code "75") (name "TX0") (class "Default")
      (node (ref "J1") (pin "4") (pinfunction "4_4") (pintype "passive"))
      (node (ref "U1") (pin "3") (pinfunction "PE1_3") (pintype "bidirectional"))
    )
    (net (code "76") (name "VUSB") (class "Default")
      (node (ref "D1") (pin "A") (pinfunction "A_A") (pintype "passive"))
      (node (ref "J1") (pin "1") (pinfunction "1_1") (pintype "passive"))
    )
    (net (code "77") (name "XTAL1") (class "Default")
      (node (ref "U1") (pin "24") (pinfunction "XTAL1_24") (pintype "input"))
      (node (ref "Y1") (pin "1") (pinfunction "1_1") (pintype "passive"))
    )
    (net (code "78") (name "unconnected-(J2-Pad2)") (class "Default")
      (node (ref "J2") (pin "2") (pinfunction "2_2") (pintype "passive"))
    )
    (net (code "79") (name "unconnected-(J2-Pad3)") (class "Default")
      (node (ref "J2") (pin "3") (pinfunction "3_3") (pintype "passive"))
    )
    (net (code "80") (name "unconnected-(J2-Pad5)") (class "Default")
      (node (ref "J2") (pin "5") (pinfunction "5_5") (pintype "passive"))
    )
    (net (code "81") (name "unconnected-(J2-Pad6)") (class "Default")
      (node (ref "J2") (pin "6") (pinfunction "6_6") (pintype "passive"))
    )
    (net (code "82") (name "unconnected-(J2-Pad7)") (class "Default")
      (node (ref "J2") (pin "7") (pinfunction "7_7") (pintype "passive"))
    )
    (net (code "83") (name "unconnected-(J2-Pad8)") (class "Default")
      (node (ref "J2") (pin "8") (pinfunction "8_8") (pintype "passive"))
    )
    (net (code "84") (name "unconnected-(J2-Pad9)") (class "Default")
      (node (ref "J2") (pin "9") (pinfunction "9_9") (pintype "passive"))
    )
    (net (code "85") (name "unconnected-(J2-Pad10)") (class "Default")
      (node (ref "J2") (pin "10") (pinfunction "10_10") (pintype "passive"))
    )
    (net (code "86") (name "unconnected-(J2-Pad11)") (class "Default")
      (node (ref "J2") (pin "11") (pinfunction "11_11") (pintype "passive"))
    )
    (net (code "87") (name "unconnected-(J2-Pad12)") (class "Default")
      (node (ref "J2") (pin "12") (pinfunction "12_12") (pintype "passive"))
    )
    (net (code "88") (name "unconnected-(J2-Pad13)") (class "Default")
      (node (ref "J2") (pin "13") (pinfunction "13_13") (pintype "passive"))
    )
    (net (code "89") (name "unconnected-(J2-Pad14)") (class "Default")
      (node (ref "J2") (pin "14") (pinfunction "14_14") (pintype "passive"))
    )
    (net (code "90") (name "unconnected-(J2-Pad15)") (class "Default")
      (node (ref "J2") (pin "15") (pinfunction "15_15") (pintype "passive"))
    )
    (net (code "91") (name "unconnected-(J2-Pad18)") (class "Default")
      (node (ref "J2") (pin "18") (pinfunction "18_18") (pintype "passive"))
    )
    (net (code "92") (name "unconnected-(J2-Pad19)") (class "Default")
      (node (ref "J2") (pin "19") (pinfunction "19_19") (pintype "passive"))
    )
    (net (code "93") (name "unconnected-(J2-Pad20)") (class "Default")
      (node (ref "J2") (pin "20") (pinfunction "20_20") (pintype "passive"))
    )
    (net (code "94") (name "unconnected-(J2-Pad21)") (class "Default")
      (node (ref "J2") (pin "21") (pinfunction "21_21") (pintype "passive"))
    )
    (net (code "95") (name "unconnected-(J3-Pad1)") (class "Default")
      (node (ref "J3") (pin "1") (pinfunction "1_1") (pintype "passive"))
    )
    (net (code "96") (name "unconnected-(J3-Pad2)") (class "Default")
      (node (ref "J3") (pin "2") (pinfunction "2_2") (pintype "passive"))
    )
    (net (code "97") (name "unconnected-(J3-Pad3)") (class "Default")
      (node (ref "J3") (pin "3") (pinfunction "3_3") (pintype "passive"))
    )
    (net (code "98") (name "unconnected-(J3-Pad4)") (class "Default")
      (node (ref "J3") (pin "4") (pinfunction "4_4") (pintype "passive"))
    )
    (net (code "99") (name "unconnected-(J3-Pad5)") (class "Default")
      (node (ref "J3") (pin "5") (pinfunction "5_5") (pintype "passive"))
    )
    (net (code "100") (name "unconnected-(J3-Pad6)") (class "Default")
      (node (ref "J3") (pin "6") (pinfunction "6_6") (pintype "passive"))
    )
    (net (code "101") (name "unconnected-(J3-Pad7)") (class "Default")
      (node (ref "J3") (pin "7") (pinfunction "7_7") (pintype "passive"))
    )
    (net (code "102") (name "unconnected-(J3-Pad8)") (class "Default")
      (node (ref "J3") (pin "8") (pinfunction "8_8") (pintype "passive"))
    )
    (net (code "103") (name "unconnected-(J3-Pad9)") (class "Default")
      (node (ref "J3") (pin "9") (pinfunction "9_9") (pintype "passive"))
    )
    (net (code "104") (name "unconnected-(J3-Pad10)") (class "Default")
      (node (ref "J3") (pin "10") (pinfunction "10_10") (pintype "passive"))
    )
    (net (code "105") (name "unconnected-(J3-Pad11)") (class "Default")
      (node (ref "J3") (pin "11") (pinfunction "11_11") (pintype "passive"))
    )
    (net (code "106") (name "unconnected-(J3-Pad12)") (class "Default")
      (node (ref "J3") (pin "12") (pinfunction "12_12") (pintype "passive"))
    )
    (net (code "107") (name "unconnected-(J3-Pad13)") (class "Default")
      (node (ref "J3") (pin "13") (pinfunction "13_13") (pintype "passive"))
    )
    (net (code "108") (name "unconnected-(J3-Pad14)") (class "Default")
      (node (ref "J3") (pin "14") (pinfunction "14_14") (pintype "passive"))
    )
    (net (code "109") (name "unconnected-(J3-Pad15)") (class "Default")
      (node (ref "J3") (pin "15") (pinfunction "15_15") (pintype "passive"))
    )
    (net (code "110") (name "unconnected-(J3-Pad16)") (class "Default")
      (node (ref "J3") (pin "16") (pinfunction "16_16") (pintype "passive"))
    )
    (net (code "111") (name "unconnected-(J3-Pad17)") (class "Default")
      (node (ref "J3") (pin "17") (pinfunction "17_17") (pintype "passive"))
    )
    (net (code "112") (name "unconnected-(J3-Pad18)") (class "Default")
      (node (ref "J3") (pin "18") (pinfunction "18_18") (pintype "passive"))
    )
    (net (code "113") (name "unconnected-(J3-Pad19)") (class "Default")
      (node (ref "J3") (pin "19") (pinfunction "19_19") (pintype "passive"))
    )
    (net (code "114") (name "unconnected-(J3-Pad20)") (class "Default")
      (node (ref "J3") (pin "20") (pinfunction "20_20") (pintype "passive"))
    )
    (net (code "115") (name "unconnected-(J3-Pad21)") (class "Default")
      (node (ref "J3") (pin "21") (pinfunction "21_21") (pintype "passive"))
    )
    (net (code "116") (name "unconnected-(J3-Pad22)") (class "Default")
      (node (ref "J3") (pin "22") (pinfunction "22_22") (pintype "passive"))
    )
    (net (code "117") (name "unconnected-(J3-Pad23)") (class "Default")
      (node (ref "J3") (pin "23") (pinfunction "23_23") (pintype "passive"))
    )
    (net (code "118") (name "unconnected-(J3-Pad24)") (class "Default")
      (node (ref "J3") (pin "24") (pinfunction "24_24") (pintype "passive"))
    )
    (net (code "119") (name "unconnected-(U$46-PadDOUT)") (class "Default")
      (node (ref "U$46") (pin "DOUT") (pinfunction "DOUT_DOUT") (pintype "bidirectional"))
    )
    (net (code "120") (name "unconnected-(U$47-P$6-PadP$4)") (class "Default")
      (node (ref "U$47") (pin "P$4") (pinfunction "P$6_P$4") (pintype "bidirectional"))
    )
    (net (code "121") (name "unconnected-(U$47-PadP$1)") (class "Default")
      (node (ref "U$47") (pin "P$1") (pinfunction "P$1_P$1") (pintype "bidirectional"))
    )
    (net (code "122") (name "unconnected-(U1-~{PEN}-Pad1)") (class "Default")
      (node (ref "U1") (pin "1") (pinfunction "~{PEN}_1") (pintype "input"))
    )
    (net (code "123") (name "unconnected-(U2-A2-PadP$4)") (class "Default")
      (node (ref "U2") (pin "P$4") (pinfunction "A2_P$4") (pintype "bidirectional"))
    )
    (net (code "124") (name "unconnected-(U2-B2-PadP$1)") (class "Default")
      (node (ref "U2") (pin "P$1") (pinfunction "B2_P$1") (pintype "bidirectional"))
    )
    (net (code "125") (name "unconnected-(U2-OE-PadP$6)") (class "Default")
      (node (ref "U2") (pin "P$6") (pinfunction "OE_P$6") (pintype "bidirectional"))
    )
  )
)
